# stamp-fixed-smt-mk-1_1.net
KiCad netlist of a schematic drawn in EAGLE
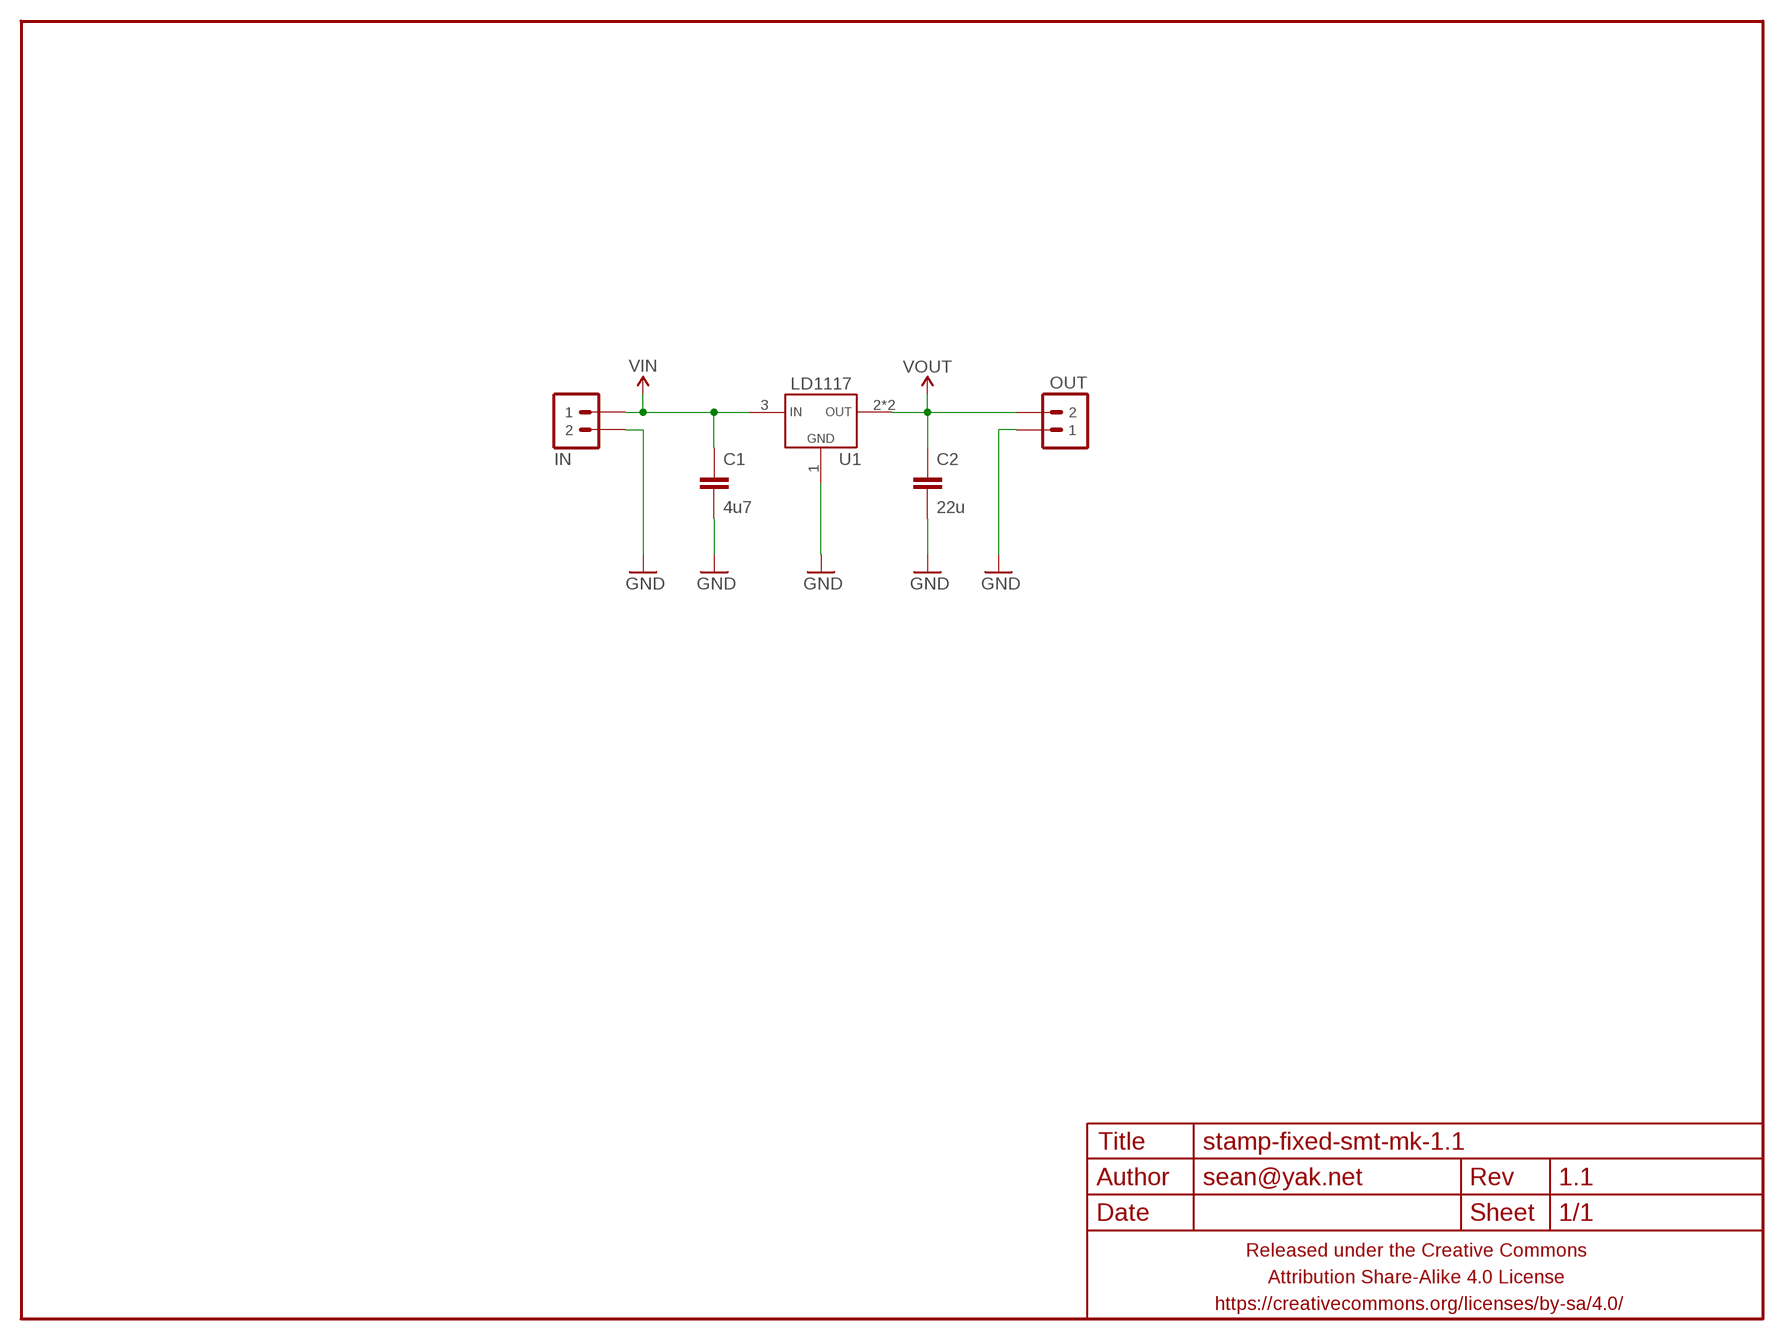
[diagram p0: schematic, sheet 1]

(export (version "E")
  (design (tool "Eeschema 10.0.6"))
  (components
    (comp (ref "C1")
      (value "4u7")
      (footprint "eagle-import:C0805-TIGHTER")
      (libsource (lib "eagle-import") (part "CAPACITOR-CERAMICC0805-TIGHTER"))
    )
    (comp (ref "C2")
      (value "22u")
      (footprint "eagle-import:C0805-TIGHTER")
      (libsource (lib "eagle-import") (part "CAPACITOR-CERAMICC0805-TIGHTER"))
    )
    (comp (ref "FRAME1")
      (value "FRAME-LETTERNO_PACKAGE")
      (footprint "eagle-import:DUMMY")
      (fields (field (name "DESIGNER") "sean@yak.net") (field (name "VERSION") "1.1"))
      (libsource (lib "eagle-import") (part "FRAME-LETTERNO_PACKAGE"))
    )
    (comp (ref "IN")
      (value "M02PTH-CENTERED-L+")
      (footprint "eagle-import:1X02-CENTER-L+")
      (libsource (lib "eagle-import") (part "M02PTH-CENTERED-L+"))
    )
    (comp (ref "OUT")
      (value "M02PTH-CENTERED-R+")
      (footprint "eagle-import:1X02-CENTER-R+")
      (libsource (lib "eagle-import") (part "M02PTH-CENTERED-R+"))
    )
    (comp (ref "U1")
      (value "LD1117")
      (footprint "eagle-import:SOT223")
      (libsource (lib "eagle-import") (part "VREG_1117SOT223"))
    )
  )
  (nets
    (net (code "1") (name "GND") (class "Default")
      (node (ref "C1") (pin "2") (pinfunction "2_2") (pintype "passive"))
      (node (ref "C2") (pin "2") (pinfunction "2_2") (pintype "passive"))
      (node (ref "IN") (pin "2") (pinfunction "2_2") (pintype "passive"))
      (node (ref "OUT") (pin "1") (pinfunction "1_1") (pintype "passive"))
      (node (ref "U1") (pin "1") (pinfunction "GND_1") (pintype "bidirectional"))
    )
    (net (code "2") (name "VIN") (class "Default")
      (node (ref "C1") (pin "1") (pinfunction "1_1") (pintype "passive"))
      (node (ref "IN") (pin "1") (pinfunction "1_1") (pintype "passive"))
      (node (ref "U1") (pin "3") (pinfunction "VIN_3") (pintype "bidirectional"))
    )
    (net (code "3") (name "VOUT") (class "Default")
      (node (ref "C2") (pin "1") (pinfunction "1_1") (pintype "passive"))
      (node (ref "OUT") (pin "2") (pinfunction "2_2") (pintype "passive"))
      (node (ref "U1") (pin "2") (pinfunction "VOUT_2") (pintype "bidirectional"))
      (node (ref "U1") (pin "4") (pinfunction "VOUT_4") (pintype "bidirectional"))
    )
  )
)
